# SCH_Beginner_project_2021-06-27.net
KiCad netlist of a schematic drawn in EasyEDA
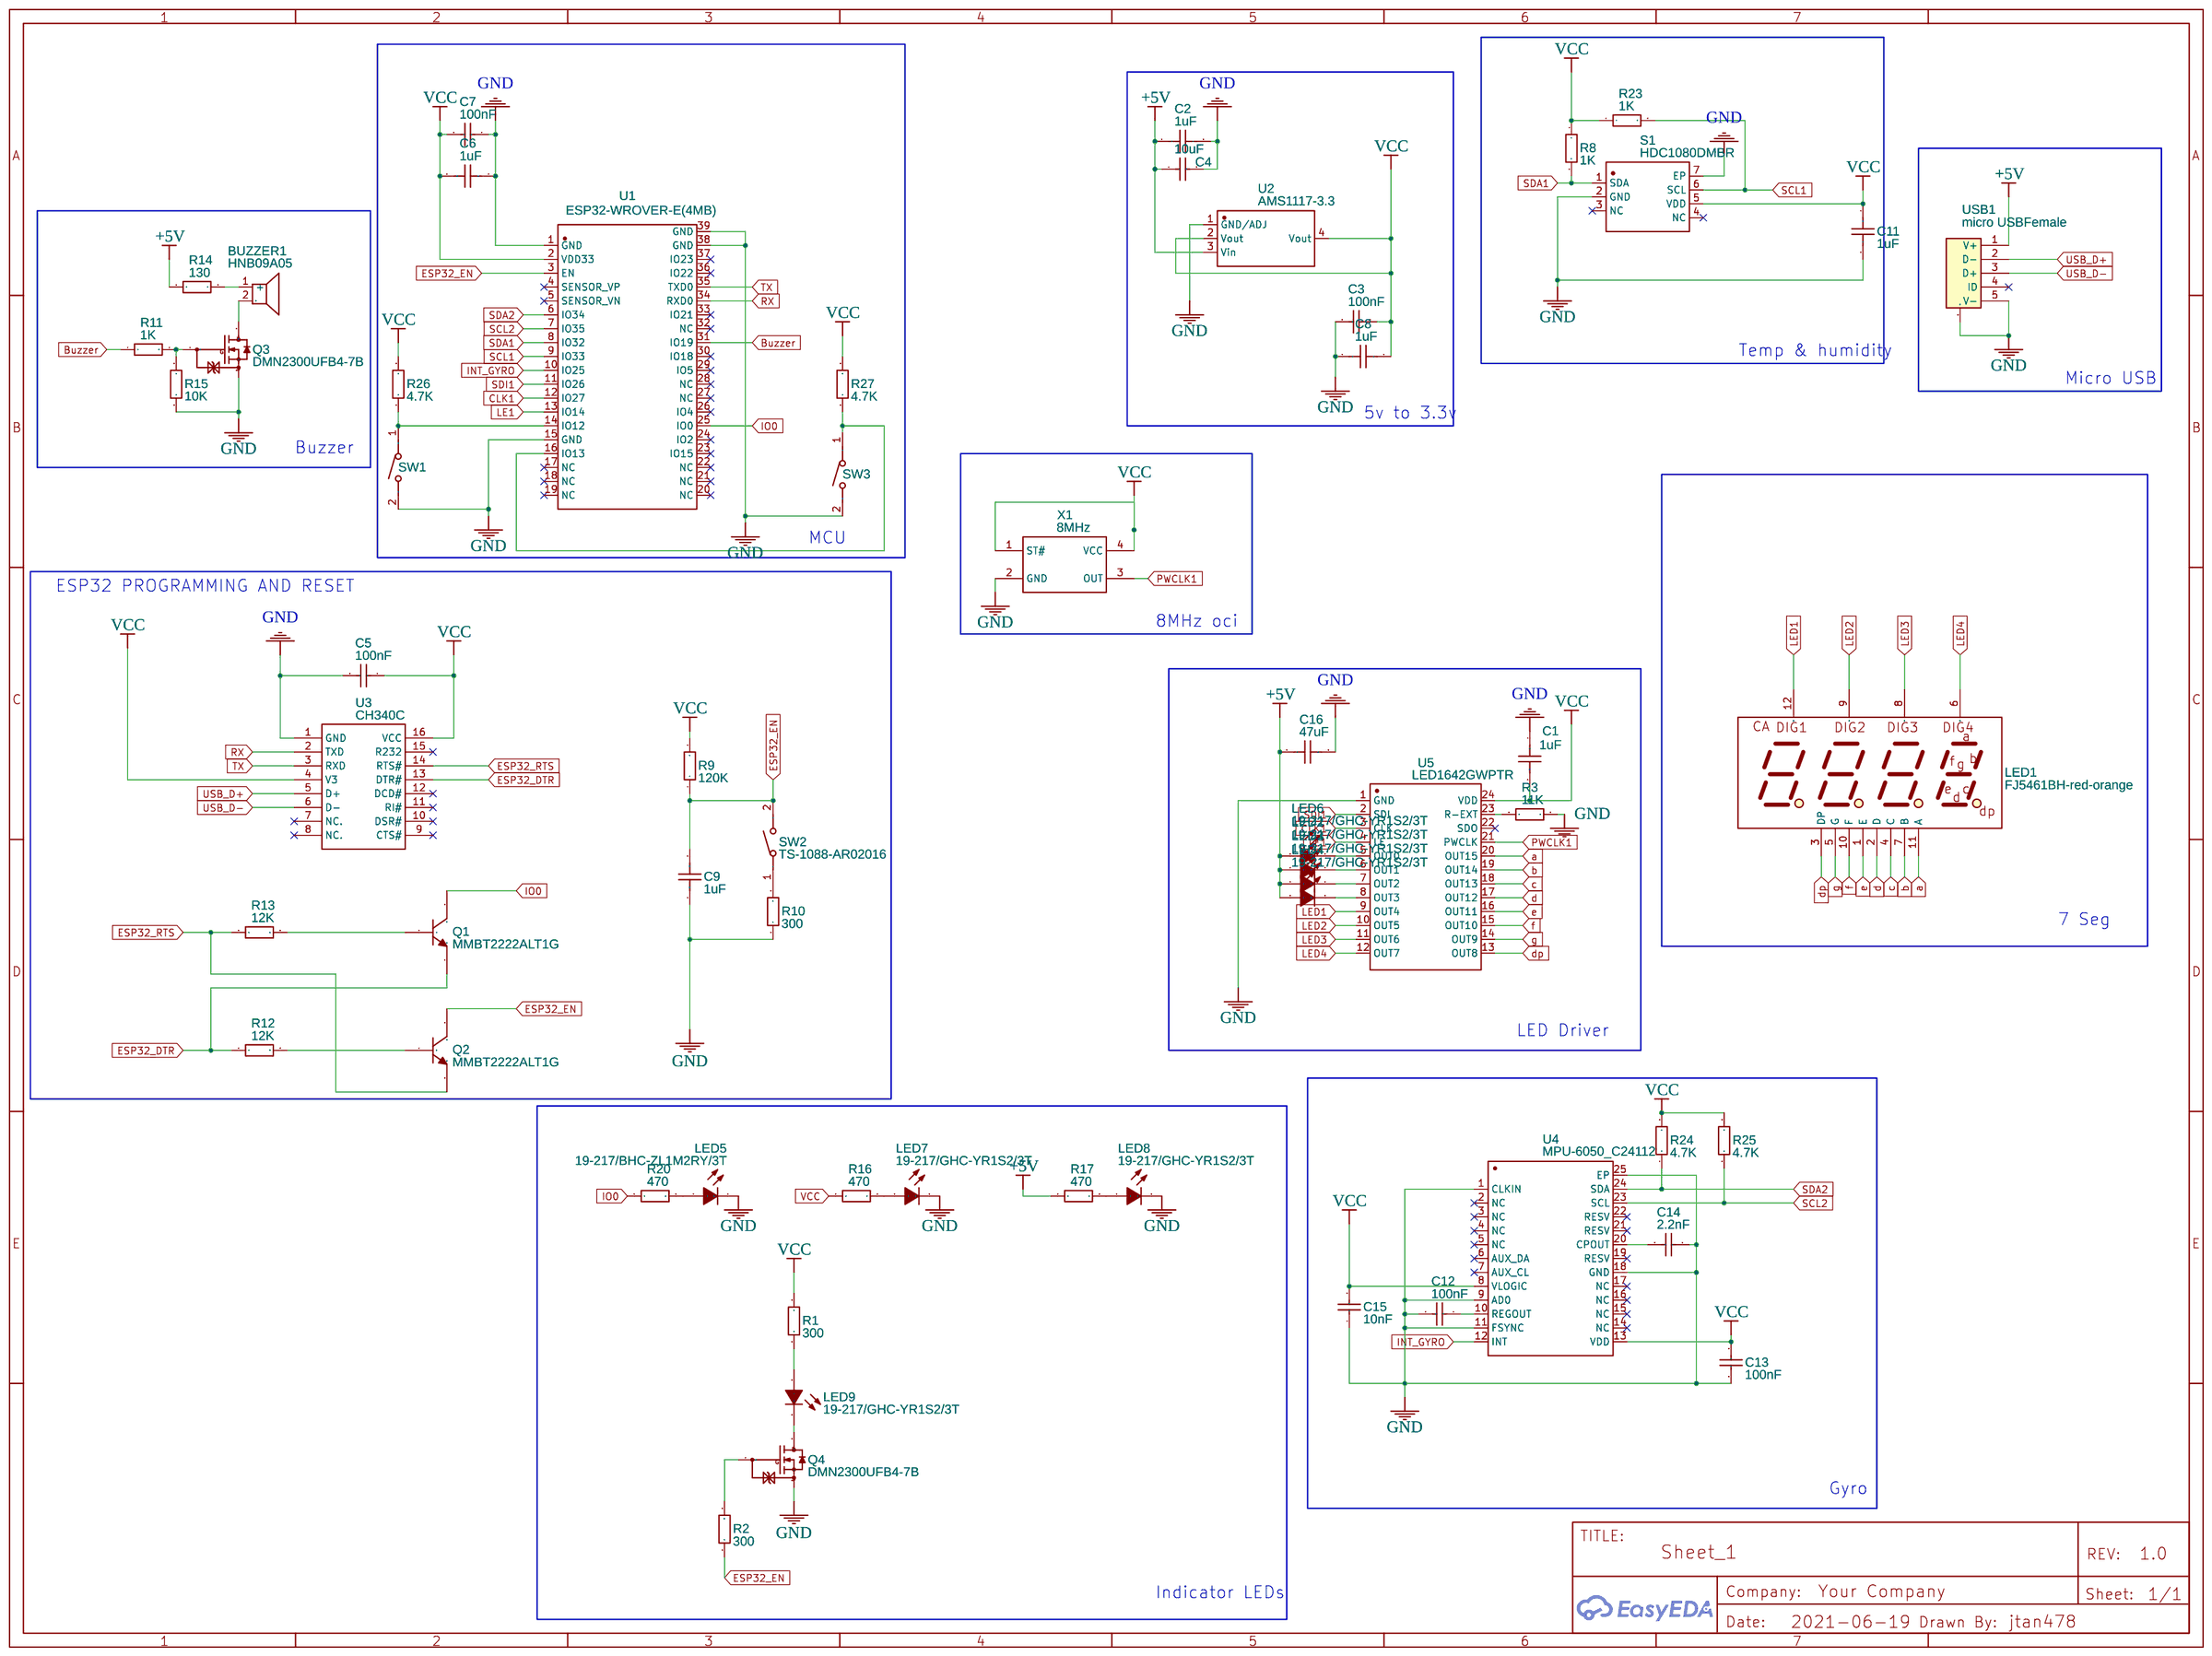
[diagram p0: schematic sheet]

(export (version "E")
  (design (tool "Eeschema 10.0.6"))
  (components
    (comp (ref "BUZZER1")
      (value "HNB09A05")
      (fields (field (name "BOM_Supplier Part") "C96493"))
      (libsource (lib "") (part "HNB09A05"))
    )
    (comp (ref "C1")
      (value "1uF")
      (fields
        (field (name "BOM_Manufacturer Part") "CL05A105KA5NQNC")
        (field (name "BOM_Supplier Part") "C52923")
      )
      (libsource (lib "") (part "CL05A105KA5NQNC"))
    )
    (comp (ref "C2")
      (value "1uF")
      (fields
        (field (name "BOM_Manufacturer Part") "CL05A105KA5NQNC")
        (field (name "BOM_Supplier Part") "C52923")
      )
      (libsource (lib "") (part "CL05A105KA5NQNC_1"))
    )
    (comp (ref "C3")
      (value "100nF")
      (fields
        (field (name "BOM_Manufacturer Part") "CL05B104KO5NNNC")
        (field (name "BOM_Supplier Part") "C1525")
      )
      (libsource (lib "") (part "CL05B104KO5NNNC"))
    )
    (comp (ref "C4")
      (value "10uF")
      (fields
        (field (name "BOM_Manufacturer Part") "CL05A106MQ5NUNC")
        (field (name "BOM_Supplier Part") "C15525")
      )
      (libsource (lib "") (part "CL05A106MQ5NUNC"))
    )
    (comp (ref "C5")
      (value "100nF")
      (fields
        (field (name "BOM_Manufacturer Part") "CL05B104KO5NNNC")
        (field (name "BOM_Supplier Part") "C1525")
      )
      (libsource (lib "") (part "CL05B104KO5NNNC"))
    )
    (comp (ref "C6")
      (value "1uF")
      (fields
        (field (name "BOM_Manufacturer Part") "CL05A105KA5NQNC")
        (field (name "BOM_Supplier Part") "C52923")
      )
      (libsource (lib "") (part "CL05A105KA5NQNC_3"))
    )
    (comp (ref "C7")
      (value "100nF")
      (fields
        (field (name "BOM_Manufacturer Part") "CL05B104KO5NNNC")
        (field (name "BOM_Supplier Part") "C1525")
      )
      (libsource (lib "") (part "CL05B104KO5NNNC"))
    )
    (comp (ref "C8")
      (value "1uF")
      (fields
        (field (name "BOM_Manufacturer Part") "CL05A105KA5NQNC")
        (field (name "BOM_Supplier Part") "C52923")
      )
      (libsource (lib "") (part "CL05A105KA5NQNC_1"))
    )
    (comp (ref "C9")
      (value "1uF")
      (fields
        (field (name "BOM_Manufacturer Part") "CL05A105KA5NQNC")
        (field (name "BOM_Supplier Part") "C52923")
      )
      (libsource (lib "") (part "CL05A105KA5NQNC_2"))
    )
    (comp (ref "C11")
      (value "1uF")
      (fields
        (field (name "BOM_Manufacturer Part") "CL05A105KA5NQNC")
        (field (name "BOM_Supplier Part") "C52923")
      )
      (libsource (lib "") (part "CL05A105KA5NQNC"))
    )
    (comp (ref "C12")
      (value "100nF")
      (fields
        (field (name "BOM_Manufacturer Part") "CL05B104KO5NNNC")
        (field (name "BOM_Supplier Part") "C1525")
      )
      (libsource (lib "") (part "CL05B104KO5NNNC"))
    )
    (comp (ref "C13")
      (value "100nF")
      (fields
        (field (name "BOM_Manufacturer Part") "CL05B104KO5NNNC")
        (field (name "BOM_Supplier Part") "C1525")
      )
      (libsource (lib "") (part "CL05B104KO5NNNC_1"))
    )
    (comp (ref "C14")
      (value "2.2nF")
      (fields
        (field (name "BOM_Manufacturer Part") "0402B222K500NT")
        (field (name "BOM_Supplier Part") "C1531")
      )
      (libsource (lib "") (part "0402B222K500NT"))
    )
    (comp (ref "C15")
      (value "10nF")
      (fields
        (field (name "BOM_Manufacturer Part") "CL05B103KB5NNNC")
        (field (name "BOM_Supplier Part") "C15195")
      )
      (libsource (lib "") (part "CL05B103KB5NNNC"))
    )
    (comp (ref "C16")
      (value "47uF")
      (fields
        (field (name "BOM_Manufacturer Part") "CL31A476MPHNNNE")
        (field (name "BOM_Supplier Part") "C96123")
      )
      (libsource (lib "") (part "CL31A476MPHNNNE"))
    )
    (comp (ref "LED1")
      (value "FJ5461BH-red-orange")
      (fields
        (field (name "BOM_Manufacturer Part") "FJ5461BH 橙红")
        (field (name "BOM_Supplier Part") "C10713")
      )
      (libsource (lib "") (part "FJ5461BH-red-orange"))
    )
    (comp (ref "LED2")
      (value "19-217/GHC-YR1S2/3T")
      (fields (field (name "BOM_Supplier Part") "C72043"))
      (libsource (lib "") (part "19-217/GHC-YR1S2/3T"))
    )
    (comp (ref "LED3")
      (value "19-217/GHC-YR1S2/3T")
      (fields (field (name "BOM_Supplier Part") "C72043"))
      (libsource (lib "") (part "19-217/GHC-YR1S2/3T"))
    )
    (comp (ref "LED4")
      (value "19-217/GHC-YR1S2/3T")
      (fields (field (name "BOM_Supplier Part") "C72043"))
      (libsource (lib "") (part "19-217/GHC-YR1S2/3T"))
    )
    (comp (ref "LED5")
      (value "19-217/BHC-ZL1M2RY/3T")
      (fields (field (name "BOM_Supplier Part") "C72041"))
      (libsource (lib "") (part "19-217/BHC-ZL1M2RY/3T"))
    )
    (comp (ref "LED6")
      (value "19-217/GHC-YR1S2/3T")
      (fields (field (name "BOM_Supplier Part") "C72043"))
      (libsource (lib "") (part "19-217/GHC-YR1S2/3T"))
    )
    (comp (ref "LED7")
      (value "19-217/GHC-YR1S2/3T")
      (fields (field (name "BOM_Supplier Part") "C72043"))
      (libsource (lib "") (part "19-217/GHC-YR1S2/3T"))
    )
    (comp (ref "LED8")
      (value "19-217/GHC-YR1S2/3T")
      (fields (field (name "BOM_Supplier Part") "C72043"))
      (libsource (lib "") (part "19-217/GHC-YR1S2/3T"))
    )
    (comp (ref "LED9")
      (value "19-217/GHC-YR1S2/3T")
      (fields (field (name "BOM_Supplier Part") "C72043"))
      (libsource (lib "") (part "19-217/GHC-YR1S2/3T_1"))
    )
    (comp (ref "Q1")
      (value "MMBT2222ALT1G")
      (fields (field (name "BOM_Supplier Part") "C82460"))
      (libsource (lib "") (part "MMBT2222ALT1G"))
    )
    (comp (ref "Q2")
      (value "MMBT2222ALT1G")
      (fields (field (name "BOM_Supplier Part") "C82460"))
      (libsource (lib "") (part "MMBT2222ALT1G"))
    )
    (comp (ref "Q3")
      (value "DMN2300UFB4-7B")
      (fields (field (name "BOM_Supplier Part") "C154728"))
      (libsource (lib "") (part "DMN2300UFB4-7B"))
    )
    (comp (ref "Q4")
      (value "DMN2300UFB4-7B")
      (fields (field (name "BOM_Supplier Part") "C154728"))
      (libsource (lib "") (part "DMN2300UFB4-7B"))
    )
    (comp (ref "R1")
      (value "300")
      (fields
        (field (name "BOM_Manufacturer Part") "0402WGF3000TCE")
        (field (name "BOM_Supplier Part") "C25102")
      )
      (libsource (lib "") (part "0402WGF3000TCE"))
    )
    (comp (ref "R2")
      (value "300")
      (fields
        (field (name "BOM_Manufacturer Part") "0402WGF3000TCE")
        (field (name "BOM_Supplier Part") "C25102")
      )
      (libsource (lib "") (part "0402WGF3000TCE"))
    )
    (comp (ref "R3")
      (value "11K")
      (fields
        (field (name "BOM_Manufacturer Part") "0603WAF1102T5E")
        (field (name "BOM_Supplier Part") "C25950")
      )
      (libsource (lib "") (part "0603WAF1102T5E"))
    )
    (comp (ref "R8")
      (value "1K")
      (fields
        (field (name "BOM_Manufacturer Part") "0603WAF1001T5E")
        (field (name "BOM_Supplier Part") "C21190")
      )
      (libsource (lib "") (part "0603WAF1001T5E"))
    )
    (comp (ref "R9")
      (value "120K")
      (fields
        (field (name "BOM_Manufacturer Part") "0402WGF1203TCE")
        (field (name "BOM_Supplier Part") "C25750")
      )
      (libsource (lib "") (part "0402WGF1203TCE"))
    )
    (comp (ref "R10")
      (value "300")
      (fields
        (field (name "BOM_Manufacturer Part") "0402WGF3000TCE")
        (field (name "BOM_Supplier Part") "C25102")
      )
      (libsource (lib "") (part "0402WGF3000TCE"))
    )
    (comp (ref "R11")
      (value "1K")
      (fields
        (field (name "BOM_Manufacturer Part") "0603WAF1001T5E")
        (field (name "BOM_Supplier Part") "C21190")
      )
      (libsource (lib "") (part "0603WAF1001T5E_1"))
    )
    (comp (ref "R12")
      (value "12K")
      (fields
        (field (name "BOM_Manufacturer Part") "0402WGF1202TCE")
        (field (name "BOM_Supplier Part") "C25752")
      )
      (libsource (lib "") (part "0402WGF1202TCE"))
    )
    (comp (ref "R13")
      (value "12K")
      (fields
        (field (name "BOM_Manufacturer Part") "0402WGF1202TCE")
        (field (name "BOM_Supplier Part") "C25752")
      )
      (libsource (lib "") (part "0402WGF1202TCE"))
    )
    (comp (ref "R14")
      (value "130")
      (fields
        (field (name "BOM_Manufacturer Part") "0603WAF1300T5E")
        (field (name "BOM_Supplier Part") "C22796")
      )
      (libsource (lib "") (part "0603WAF1300T5E"))
    )
    (comp (ref "R15")
      (value "10K")
      (fields
        (field (name "BOM_Manufacturer Part") "0603WAF1002T5E")
        (field (name "BOM_Supplier Part") "C25804")
      )
      (libsource (lib "") (part "0603WAF1002T5E"))
    )
    (comp (ref "R16")
      (value "470")
      (fields
        (field (name "BOM_Manufacturer Part") "0402WGF4700TCE")
        (field (name "BOM_Supplier Part") "C25117")
      )
      (libsource (lib "") (part "0402WGF4700TCE"))
    )
    (comp (ref "R17")
      (value "470")
      (fields
        (field (name "BOM_Manufacturer Part") "0402WGF4700TCE")
        (field (name "BOM_Supplier Part") "C25117")
      )
      (libsource (lib "") (part "0402WGF4700TCE"))
    )
    (comp (ref "R20")
      (value "470")
      (fields
        (field (name "BOM_Manufacturer Part") "0402WGF4700TCE")
        (field (name "BOM_Supplier Part") "C25117")
      )
      (libsource (lib "") (part "0402WGF4700TCE"))
    )
    (comp (ref "R23")
      (value "1K")
      (fields
        (field (name "BOM_Manufacturer Part") "0603WAF1001T5E")
        (field (name "BOM_Supplier Part") "C21190")
      )
      (libsource (lib "") (part "0603WAF1001T5E_1"))
    )
    (comp (ref "R24")
      (value "4.7K")
      (fields
        (field (name "BOM_Manufacturer Part") "0402WGF4701TCE")
        (field (name "BOM_Supplier Part") "C25900")
      )
      (libsource (lib "") (part "0402WGF4701TCE"))
    )
    (comp (ref "R25")
      (value "4.7K")
      (fields
        (field (name "BOM_Manufacturer Part") "0402WGF4701TCE")
        (field (name "BOM_Supplier Part") "C25900")
      )
      (libsource (lib "") (part "0402WGF4701TCE"))
    )
    (comp (ref "R26")
      (value "4.7K")
      (fields
        (field (name "BOM_Manufacturer Part") "0402WGF4701TCE")
        (field (name "BOM_Supplier Part") "C25900")
      )
      (libsource (lib "") (part "0402WGF4701TCE"))
    )
    (comp (ref "R27")
      (value "4.7K")
      (fields
        (field (name "BOM_Manufacturer Part") "0402WGF4701TCE")
        (field (name "BOM_Supplier Part") "C25900")
      )
      (libsource (lib "") (part "0402WGF4701TCE"))
    )
    (comp (ref "S1")
      (value "HDC1080DMBR")
      (fields (field (name "BOM_Supplier Part") "C82227"))
      (libsource (lib "") (part "HDC1080DMBR"))
    )
    (comp (ref "SW1")
      (value "TS-1088-AR02016")
      (fields (field (name "BOM_Supplier Part") "C720477"))
      (libsource (lib "") (part "TS-1088-AR02016_1"))
    )
    (comp (ref "SW2")
      (value "TS-1088-AR02016")
      (fields (field (name "BOM_Supplier Part") "C720477"))
      (libsource (lib "") (part "TS-1088-AR02016"))
    )
    (comp (ref "SW3")
      (value "TS-1088-AR02016")
      (fields (field (name "BOM_Supplier Part") "C720477"))
      (libsource (lib "") (part "TS-1088-AR02016_1"))
    )
    (comp (ref "U1")
      (value "ESP32-WROVER-E(4MB)")
      (fields (field (name "BOM_Supplier Part") "C529587"))
      (libsource (lib "") (part "ESP32-WROVER-E(4MB)"))
    )
    (comp (ref "U2")
      (value "AMS1117-3.3")
      (fields (field (name "BOM_Supplier Part") "C6186"))
      (libsource (lib "") (part "AMS1117-3.3"))
    )
    (comp (ref "U3")
      (value "CH340C")
      (fields (field (name "BOM_Supplier Part") "C84681"))
      (libsource (lib "") (part "CH340C"))
    )
    (comp (ref "U4")
      (value "MPU-6050_C24112")
      (fields (field (name "BOM_Manufacturer Part") "MPU-6050") (field (name "BOM_Supplier Part") "C24112"))
      (libsource (lib "") (part "MPU-6050_C24112"))
    )
    (comp (ref "U5")
      (value "LED1642GWPTR")
      (fields (field (name "BOM_Supplier Part") "C131193"))
      (libsource (lib "") (part "LED1642GWPTR"))
    )
    (comp (ref "USB1")
      (value "micro USBFemale")
      (fields (field (name "BOM_Supplier Part") "C10418"))
      (libsource (lib "") (part "micro USBFemale"))
    )
    (comp (ref "X1")
      (value "8MHz")
      (fields
        (field (name "BOM_Manufacturer Part") "Q33310F70055100")
        (field (name "BOM_Supplier Part") "C70556")
      )
      (libsource (lib "") (part "Q33310F70055100"))
    )
  )
  (nets
    (net (code "1") (name "+5V") (class "Default")
      (node (ref "C16") (pin "1") (pinfunction "1_1") (pintype "unspecified"))
      (node (ref "C2") (pin "1") (pinfunction "1_1") (pintype "unspecified"))
      (node (ref "C4") (pin "1") (pinfunction "1_1") (pintype "input"))
      (node (ref "LED2") (pin "1") (pinfunction "A_1") (pintype "input"))
      (node (ref "LED3") (pin "1") (pinfunction "A_1") (pintype "input"))
      (node (ref "LED4") (pin "1") (pinfunction "A_1") (pintype "input"))
      (node (ref "LED6") (pin "1") (pinfunction "A_1") (pintype "input"))
      (node (ref "R14") (pin "1") (pinfunction "1_1") (pintype "input"))
      (node (ref "R17") (pin "1") (pinfunction "1_1") (pintype "input"))
      (node (ref "U2") (pin "3") (pinfunction "Vin_3") (pintype "unspecified"))
      (node (ref "USB1") (pin "1") (pinfunction "V+_1") (pintype "unspecified"))
    )
    (net (code "2") (name "Buzzer") (class "Default")
      (node (ref "R11") (pin "1") (pinfunction "1_1") (pintype "input"))
      (node (ref "U1") (pin "31") (pinfunction "IO19_31") (pintype "unspecified"))
    )
    (net (code "3") (name "CLK1") (class "Default")
      (node (ref "U1") (pin "12") (pinfunction "IO27_12") (pintype "unspecified"))
      (node (ref "U5") (pin "3") (pinfunction "CLK_3") (pintype "unspecified"))
    )
    (net (code "4") (name "ESP32_DTR") (class "Default")
      (node (ref "Q1") (pin "2") (pinfunction "E_2") (pintype "unspecified"))
      (node (ref "R12") (pin "1") (pinfunction "1_1") (pintype "input"))
      (node (ref "U3") (pin "13") (pinfunction "DTR#_13") (pintype "unspecified"))
    )
    (net (code "5") (name "ESP32_EN") (class "Default")
      (node (ref "C9") (pin "2") (pinfunction "2_2") (pintype "unspecified"))
      (node (ref "Q2") (pin "3") (pinfunction "C_3") (pintype "unspecified"))
      (node (ref "R2") (pin "1") (pinfunction "1_1") (pintype "input"))
      (node (ref "R9") (pin "1") (pinfunction "1_1") (pintype "input"))
      (node (ref "SW2") (pin "2") (pinfunction "2_2") (pintype "unspecified"))
      (node (ref "U1") (pin "3") (pinfunction "EN_3") (pintype "unspecified"))
    )
    (net (code "6") (name "ESP32_RTS") (class "Default")
      (node (ref "Q2") (pin "2") (pinfunction "E_2") (pintype "unspecified"))
      (node (ref "R13") (pin "1") (pinfunction "1_1") (pintype "input"))
      (node (ref "U3") (pin "14") (pinfunction "RTS#_14") (pintype "unspecified"))
    )
    (net (code "7") (name "GND") (class "Default")
      (node (ref "C1") (pin "1") (pinfunction "1_1") (pintype "unspecified"))
      (node (ref "C11") (pin "2") (pinfunction "2_2") (pintype "unspecified"))
      (node (ref "C12") (pin "2") (pinfunction "2_2") (pintype "input"))
      (node (ref "C13") (pin "2") (pinfunction "2_2") (pintype "input"))
      (node (ref "C14") (pin "1") (pinfunction "1_1") (pintype "input"))
      (node (ref "C15") (pin "1") (pinfunction "1_1") (pintype "input"))
      (node (ref "C16") (pin "2") (pinfunction "2_2") (pintype "unspecified"))
      (node (ref "C2") (pin "2") (pinfunction "2_2") (pintype "unspecified"))
      (node (ref "C3") (pin "2") (pinfunction "2_2") (pintype "input"))
      (node (ref "C4") (pin "2") (pinfunction "2_2") (pintype "input"))
      (node (ref "C5") (pin "2") (pinfunction "2_2") (pintype "input"))
      (node (ref "C6") (pin "1") (pinfunction "1_1") (pintype "unspecified"))
      (node (ref "C7") (pin "1") (pinfunction "1_1") (pintype "input"))
      (node (ref "C8") (pin "1") (pinfunction "1_1") (pintype "unspecified"))
      (node (ref "C9") (pin "1") (pinfunction "1_1") (pintype "unspecified"))
      (node (ref "LED5") (pin "2") (pinfunction "C_2") (pintype "input"))
      (node (ref "LED7") (pin "2") (pinfunction "C_2") (pintype "input"))
      (node (ref "LED8") (pin "2") (pinfunction "C_2") (pintype "input"))
      (node (ref "Q3") (pin "3") (pinfunction "S_3") (pintype "unspecified"))
      (node (ref "Q4") (pin "3") (pinfunction "S_3") (pintype "unspecified"))
      (node (ref "R10") (pin "1") (pinfunction "1_1") (pintype "input"))
      (node (ref "R15") (pin "2") (pinfunction "2_2") (pintype "input"))
      (node (ref "R3") (pin "2") (pinfunction "2_2") (pintype "input"))
      (node (ref "S1") (pin "2") (pinfunction "GND_2") (pintype "unspecified"))
      (node (ref "S1") (pin "7") (pinfunction "EP_7") (pintype "unspecified"))
      (node (ref "SW1") (pin "2") (pinfunction "2_2") (pintype "unspecified"))
      (node (ref "SW3") (pin "2") (pinfunction "2_2") (pintype "unspecified"))
      (node (ref "U1") (pin "1") (pinfunction "GND_1") (pintype "unspecified"))
      (node (ref "U1") (pin "15") (pinfunction "GND_15") (pintype "unspecified"))
      (node (ref "U1") (pin "38") (pinfunction "GND_38") (pintype "unspecified"))
      (node (ref "U1") (pin "39") (pinfunction "GND_39") (pintype "unspecified"))
      (node (ref "U2") (pin "1") (pinfunction "GND/ADJ_1") (pintype "unspecified"))
      (node (ref "U3") (pin "1") (pinfunction "GND_1") (pintype "unspecified"))
      (node (ref "U4") (pin "1") (pinfunction "CLKIN_1") (pintype "unspecified"))
      (node (ref "U4") (pin "11") (pinfunction "FSYNC_11") (pintype "unspecified"))
      (node (ref "U4") (pin "18") (pinfunction "GND_18") (pintype "unspecified"))
      (node (ref "U4") (pin "25") (pinfunction "EP_25") (pintype "unspecified"))
      (node (ref "U4") (pin "9") (pinfunction "AD0_9") (pintype "unspecified"))
      (node (ref "U5") (pin "1") (pinfunction "GND_1") (pintype "unspecified"))
      (node (ref "USB1") (pin "0") (pinfunction "MTN_0") (pintype "input"))
      (node (ref "USB1") (pin "5") (pinfunction "V-_5") (pintype "unspecified"))
      (node (ref "X1") (pin "2") (pinfunction "GND_2") (pintype "unspecified"))
    )
    (net (code "8") (name "INT_GYRO") (class "Default")
      (node (ref "U1") (pin "10") (pinfunction "IO25_10") (pintype "unspecified"))
      (node (ref "U4") (pin "12") (pinfunction "INT_12") (pintype "unspecified"))
    )
    (net (code "9") (name "IO0") (class "Default")
      (node (ref "Q1") (pin "3") (pinfunction "C_3") (pintype "unspecified"))
      (node (ref "R20") (pin "1") (pinfunction "1_1") (pintype "input"))
      (node (ref "U1") (pin "25") (pinfunction "IO0_25") (pintype "unspecified"))
    )
    (net (code "10") (name "LE1") (class "Default")
      (node (ref "U1") (pin "13") (pinfunction "IO14_13") (pintype "unspecified"))
      (node (ref "U5") (pin "4") (pinfunction "LE_4") (pintype "unspecified"))
    )
    (net (code "11") (name "LED1") (class "Default")
      (node (ref "LED1") (pin "12") (pinfunction "DIG1_12") (pintype "input"))
      (node (ref "U5") (pin "9") (pinfunction "OUT4_9") (pintype "unspecified"))
    )
    (net (code "12") (name "LED2") (class "Default")
      (node (ref "LED1") (pin "9") (pinfunction "DIG2_9") (pintype "input"))
      (node (ref "U5") (pin "10") (pinfunction "OUT5_10") (pintype "unspecified"))
    )
    (net (code "13") (name "LED3") (class "Default")
      (node (ref "LED1") (pin "8") (pinfunction "DIG3_8") (pintype "input"))
      (node (ref "U5") (pin "11") (pinfunction "OUT6_11") (pintype "unspecified"))
    )
    (net (code "14") (name "LED4") (class "Default")
      (node (ref "LED1") (pin "6") (pinfunction "DIG4_6") (pintype "input"))
      (node (ref "U5") (pin "12") (pinfunction "OUT7_12") (pintype "unspecified"))
    )
    (net (code "15") (name "Net-(BUZZER1-+)") (class "Default")
      (node (ref "BUZZER1") (pin "1") (pinfunction "+_1") (pintype "unspecified"))
      (node (ref "R14") (pin "2") (pinfunction "2_2") (pintype "input"))
    )
    (net (code "16") (name "Net-(LED2-C)") (class "Default")
      (node (ref "LED2") (pin "2") (pinfunction "C_2") (pintype "input"))
      (node (ref "U5") (pin "6") (pinfunction "OUT1_6") (pintype "unspecified"))
    )
    (net (code "17") (name "Net-(LED3-C)") (class "Default")
      (node (ref "LED3") (pin "2") (pinfunction "C_2") (pintype "input"))
      (node (ref "U5") (pin "7") (pinfunction "OUT2_7") (pintype "unspecified"))
    )
    (net (code "18") (name "Net-(LED4-C)") (class "Default")
      (node (ref "LED4") (pin "2") (pinfunction "C_2") (pintype "input"))
      (node (ref "U5") (pin "8") (pinfunction "OUT3_8") (pintype "unspecified"))
    )
    (net (code "19") (name "Net-(LED5-A)") (class "Default")
      (node (ref "LED5") (pin "1") (pinfunction "A_1") (pintype "input"))
      (node (ref "R20") (pin "2") (pinfunction "2_2") (pintype "input"))
    )
    (net (code "20") (name "Net-(LED6-C)") (class "Default")
      (node (ref "LED6") (pin "2") (pinfunction "C_2") (pintype "input"))
      (node (ref "U5") (pin "5") (pinfunction "OUT0_5") (pintype "unspecified"))
    )
    (net (code "21") (name "Net-(LED7-A)") (class "Default")
      (node (ref "LED7") (pin "1") (pinfunction "A_1") (pintype "input"))
      (node (ref "R16") (pin "2") (pinfunction "2_2") (pintype "input"))
    )
    (net (code "22") (name "Net-(LED8-A)") (class "Default")
      (node (ref "LED8") (pin "1") (pinfunction "A_1") (pintype "input"))
      (node (ref "R17") (pin "2") (pinfunction "2_2") (pintype "input"))
    )
    (net (code "23") (name "Net-(LED9-A)") (class "Default")
      (node (ref "LED9") (pin "1") (pinfunction "A_1") (pintype "input"))
      (node (ref "R1") (pin "1") (pinfunction "1_1") (pintype "input"))
    )
    (net (code "24") (name "Net-(LED9-C)") (class "Default")
      (node (ref "LED9") (pin "2") (pinfunction "C_2") (pintype "input"))
      (node (ref "Q4") (pin "2") (pinfunction "D_2") (pintype "unspecified"))
    )
    (net (code "25") (name "Net-(Q1-B)") (class "Default")
      (node (ref "Q1") (pin "1") (pinfunction "B_1") (pintype "unspecified"))
      (node (ref "R13") (pin "2") (pinfunction "2_2") (pintype "input"))
    )
    (net (code "26") (name "Net-(Q2-B)") (class "Default")
      (node (ref "Q2") (pin "1") (pinfunction "B_1") (pintype "unspecified"))
      (node (ref "R12") (pin "2") (pinfunction "2_2") (pintype "input"))
    )
    (net (code "27") (name "Net-(Q3-D)") (class "Default")
      (node (ref "BUZZER1") (pin "2") (pinfunction "2_2") (pintype "unspecified"))
      (node (ref "Q3") (pin "2") (pinfunction "D_2") (pintype "unspecified"))
    )
    (net (code "28") (name "Net-(Q3-G)") (class "Default")
      (node (ref "Q3") (pin "1") (pinfunction "G_1") (pintype "unspecified"))
      (node (ref "R11") (pin "2") (pinfunction "2_2") (pintype "input"))
      (node (ref "R15") (pin "1") (pinfunction "1_1") (pintype "input"))
    )
    (net (code "29") (name "Net-(Q4-G)") (class "Default")
      (node (ref "Q4") (pin "1") (pinfunction "G_1") (pintype "unspecified"))
      (node (ref "R2") (pin "2") (pinfunction "2_2") (pintype "input"))
    )
    (net (code "30") (name "Net-(R10-Pad2)") (class "Default")
      (node (ref "R10") (pin "2") (pinfunction "2_2") (pintype "input"))
      (node (ref "SW2") (pin "1") (pinfunction "1_1") (pintype "unspecified"))
    )
    (net (code "31") (name "Net-(U1-IO12)") (class "Default")
      (node (ref "R26") (pin "1") (pinfunction "1_1") (pintype "input"))
      (node (ref "SW1") (pin "1") (pinfunction "1_1") (pintype "unspecified"))
      (node (ref "U1") (pin "14") (pinfunction "IO12_14") (pintype "unspecified"))
    )
    (net (code "32") (name "Net-(U1-IO13)") (class "Default")
      (node (ref "R27") (pin "1") (pinfunction "1_1") (pintype "input"))
      (node (ref "SW3") (pin "1") (pinfunction "1_1") (pintype "unspecified"))
      (node (ref "U1") (pin "16") (pinfunction "IO13_16") (pintype "unspecified"))
    )
    (net (code "33") (name "Net-(U4-CPOUT)") (class "Default")
      (node (ref "C14") (pin "2") (pinfunction "2_2") (pintype "input"))
      (node (ref "U4") (pin "20") (pinfunction "CPOUT_20") (pintype "unspecified"))
    )
    (net (code "34") (name "Net-(U4-REGOUT)") (class "Default")
      (node (ref "C12") (pin "1") (pinfunction "1_1") (pintype "input"))
      (node (ref "U4") (pin "10") (pinfunction "REGOUT_10") (pintype "unspecified"))
    )
    (net (code "35") (name "Net-(U5-R-EXT)") (class "Default")
      (node (ref "R3") (pin "1") (pinfunction "1_1") (pintype "input"))
      (node (ref "U5") (pin "23") (pinfunction "R-EXT_23") (pintype "unspecified"))
    )
    (net (code "36") (name "PWCLK1") (class "Default")
      (node (ref "U5") (pin "21") (pinfunction "PWCLK_21") (pintype "unspecified"))
      (node (ref "X1") (pin "3") (pinfunction "OUT_3") (pintype "unspecified"))
    )
    (net (code "37") (name "RX") (class "Default")
      (node (ref "U1") (pin "34") (pinfunction "RXD0_34") (pintype "unspecified"))
      (node (ref "U3") (pin "2") (pinfunction "TXD_2") (pintype "unspecified"))
    )
    (net (code "38") (name "SCL1") (class "Default")
      (node (ref "R23") (pin "2") (pinfunction "2_2") (pintype "input"))
      (node (ref "S1") (pin "6") (pinfunction "SCL_6") (pintype "unspecified"))
      (node (ref "U1") (pin "9") (pinfunction "IO33_9") (pintype "unspecified"))
    )
    (net (code "39") (name "SCL2") (class "Default")
      (node (ref "R25") (pin "1") (pinfunction "1_1") (pintype "input"))
      (node (ref "U1") (pin "7") (pinfunction "IO35_7") (pintype "unspecified"))
      (node (ref "U4") (pin "23") (pinfunction "SCL_23") (pintype "unspecified"))
    )
    (net (code "40") (name "SDA1") (class "Default")
      (node (ref "R8") (pin "2") (pinfunction "2_2") (pintype "input"))
      (node (ref "S1") (pin "1") (pinfunction "SDA_1") (pintype "unspecified"))
      (node (ref "U1") (pin "8") (pinfunction "IO32_8") (pintype "unspecified"))
    )
    (net (code "41") (name "SDA2") (class "Default")
      (node (ref "R24") (pin "1") (pinfunction "1_1") (pintype "input"))
      (node (ref "U1") (pin "6") (pinfunction "IO34_6") (pintype "unspecified"))
      (node (ref "U4") (pin "24") (pinfunction "SDA_24") (pintype "unspecified"))
    )
    (net (code "42") (name "SDI1") (class "Default")
      (node (ref "U1") (pin "11") (pinfunction "IO26_11") (pintype "unspecified"))
      (node (ref "U5") (pin "2") (pinfunction "SDI_2") (pintype "unspecified"))
    )
    (net (code "43") (name "TX") (class "Default")
      (node (ref "U1") (pin "35") (pinfunction "TXD0_35") (pintype "unspecified"))
      (node (ref "U3") (pin "3") (pinfunction "RXD_3") (pintype "unspecified"))
    )
    (net (code "44") (name "USB_D+") (class "Default")
      (node (ref "U3") (pin "5") (pinfunction "D+_5") (pintype "unspecified"))
      (node (ref "USB1") (pin "2") (pinfunction "D-_2") (pintype "unspecified"))
    )
    (net (code "45") (name "USB_D-") (class "Default")
      (node (ref "U3") (pin "6") (pinfunction "D-_6") (pintype "unspecified"))
      (node (ref "USB1") (pin "3") (pinfunction "D+_3") (pintype "unspecified"))
    )
    (net (code "46") (name "VCC") (class "Default")
      (node (ref "C1") (pin "2") (pinfunction "2_2") (pintype "unspecified"))
      (node (ref "C11") (pin "1") (pinfunction "1_1") (pintype "unspecified"))
      (node (ref "C13") (pin "1") (pinfunction "1_1") (pintype "input"))
      (node (ref "C15") (pin "2") (pinfunction "2_2") (pintype "input"))
      (node (ref "C3") (pin "1") (pinfunction "1_1") (pintype "input"))
      (node (ref "C5") (pin "1") (pinfunction "1_1") (pintype "input"))
      (node (ref "C6") (pin "2") (pinfunction "2_2") (pintype "unspecified"))
      (node (ref "C7") (pin "2") (pinfunction "2_2") (pintype "input"))
      (node (ref "C8") (pin "2") (pinfunction "2_2") (pintype "unspecified"))
      (node (ref "R1") (pin "2") (pinfunction "2_2") (pintype "input"))
      (node (ref "R16") (pin "1") (pinfunction "1_1") (pintype "input"))
      (node (ref "R23") (pin "1") (pinfunction "1_1") (pintype "input"))
      (node (ref "R24") (pin "2") (pinfunction "2_2") (pintype "input"))
      (node (ref "R25") (pin "2") (pinfunction "2_2") (pintype "input"))
      (node (ref "R26") (pin "2") (pinfunction "2_2") (pintype "input"))
      (node (ref "R27") (pin "2") (pinfunction "2_2") (pintype "input"))
      (node (ref "R8") (pin "1") (pinfunction "1_1") (pintype "input"))
      (node (ref "R9") (pin "2") (pinfunction "2_2") (pintype "input"))
      (node (ref "S1") (pin "5") (pinfunction "VDD_5") (pintype "unspecified"))
      (node (ref "U1") (pin "2") (pinfunction "VDD33_2") (pintype "unspecified"))
      (node (ref "U2") (pin "2") (pinfunction "Vout_2") (pintype "unspecified"))
      (node (ref "U2") (pin "4") (pinfunction "Vout_4") (pintype "unspecified"))
      (node (ref "U3") (pin "16") (pinfunction "VCC_16") (pintype "unspecified"))
      (node (ref "U3") (pin "4") (pinfunction "V3_4") (pintype "unspecified"))
      (node (ref "U4") (pin "13") (pinfunction "VDD_13") (pintype "unspecified"))
      (node (ref "U4") (pin "8") (pinfunction "VLOGIC_8") (pintype "unspecified"))
      (node (ref "U5") (pin "24") (pinfunction "VDD_24") (pintype "unspecified"))
      (node (ref "X1") (pin "1") (pinfunction "ST#_1") (pintype "unspecified"))
      (node (ref "X1") (pin "4") (pinfunction "VCC_4") (pintype "unspecified"))
    )
    (net (code "47") (name "a") (class "Default")
      (node (ref "LED1") (pin "11") (pinfunction "A_11") (pintype "input"))
      (node (ref "U5") (pin "20") (pinfunction "OUT15_20") (pintype "unspecified"))
    )
    (net (code "48") (name "b") (class "Default")
      (node (ref "LED1") (pin "7") (pinfunction "B_7") (pintype "input"))
      (node (ref "U5") (pin "19") (pinfunction "OUT14_19") (pintype "unspecified"))
    )
    (net (code "49") (name "c") (class "Default")
      (node (ref "LED1") (pin "4") (pinfunction "C_4") (pintype "input"))
      (node (ref "U5") (pin "18") (pinfunction "OUT13_18") (pintype "unspecified"))
    )
    (net (code "50") (name "d") (class "Default")
      (node (ref "LED1") (pin "2") (pinfunction "D_2") (pintype "input"))
      (node (ref "U5") (pin "17") (pinfunction "OUT12_17") (pintype "unspecified"))
    )
    (net (code "51") (name "dp") (class "Default")
      (node (ref "LED1") (pin "3") (pinfunction "DP_3") (pintype "input"))
      (node (ref "U5") (pin "13") (pinfunction "OUT8_13") (pintype "unspecified"))
    )
    (net (code "52") (name "e") (class "Default")
      (node (ref "LED1") (pin "1") (pinfunction "E_1") (pintype "input"))
      (node (ref "U5") (pin "16") (pinfunction "OUT11_16") (pintype "unspecified"))
    )
    (net (code "53") (name "f") (class "Default")
      (node (ref "LED1") (pin "10") (pinfunction "F_10") (pintype "input"))
      (node (ref "U5") (pin "15") (pinfunction "OUT10_15") (pintype "unspecified"))
    )
    (net (code "54") (name "g") (class "Default")
      (node (ref "LED1") (pin "5") (pinfunction "G_5") (pintype "input"))
      (node (ref "U5") (pin "14") (pinfunction "OUT9_14") (pintype "unspecified"))
    )
    (net (code "55") (name "unconnected-(S1-NC-Pad3)") (class "Default")
      (node (ref "S1") (pin "3") (pinfunction "NC_3") (pintype "unspecified+no_connect"))
    )
    (net (code "56") (name "unconnected-(S1-NC-Pad4)") (class "Default")
      (node (ref "S1") (pin "4") (pinfunction "NC_4") (pintype "unspecified+no_connect"))
    )
    (net (code "57") (name "unconnected-(U1-IO2-Pad24)") (class "Default")
      (node (ref "U1") (pin "24") (pinfunction "IO2_24") (pintype "unspecified+no_connect"))
    )
    (net (code "58") (name "unconnected-(U1-IO4-Pad26)") (class "Default")
      (node (ref "U1") (pin "26") (pinfunction "IO4_26") (pintype "unspecified+no_connect"))
    )
    (net (code "59") (name "unconnected-(U1-IO5-Pad29)") (class "Default")
      (node (ref "U1") (pin "29") (pinfunction "IO5_29") (pintype "unspecified+no_connect"))
    )
    (net (code "60") (name "unconnected-(U1-IO15-Pad23)") (class "Default")
      (node (ref "U1") (pin "23") (pinfunction "IO15_23") (pintype "unspecified+no_connect"))
    )
    (net (code "61") (name "unconnected-(U1-IO18-Pad30)") (class "Default")
      (node (ref "U1") (pin "30") (pinfunction "IO18_30") (pintype "unspecified+no_connect"))
    )
    (net (code "62") (name "unconnected-(U1-IO21-Pad33)") (class "Default")
      (node (ref "U1") (pin "33") (pinfunction "IO21_33") (pintype "unspecified+no_connect"))
    )
    (net (code "63") (name "unconnected-(U1-IO22-Pad36)") (class "Default")
      (node (ref "U1") (pin "36") (pinfunction "IO22_36") (pintype "unspecified+no_connect"))
    )
    (net (code "64") (name "unconnected-(U1-IO23-Pad37)") (class "Default")
      (node (ref "U1") (pin "37") (pinfunction "IO23_37") (pintype "unspecified+no_connect"))
    )
    (net (code "65") (name "unconnected-(U1-NC-Pad17)") (class "Default")
      (node (ref "U1") (pin "17") (pinfunction "NC_17") (pintype "unspecified+no_connect"))
    )
    (net (code "66") (name "unconnected-(U1-NC-Pad18)") (class "Default")
      (node (ref "U1") (pin "18") (pinfunction "NC_18") (pintype "unspecified+no_connect"))
    )
    (net (code "67") (name "unconnected-(U1-NC-Pad19)") (class "Default")
      (node (ref "U1") (pin "19") (pinfunction "NC_19") (pintype "unspecified+no_connect"))
    )
    (net (code "68") (name "unconnected-(U1-NC-Pad20)") (class "Default")
      (node (ref "U1") (pin "20") (pinfunction "NC_20") (pintype "unspecified+no_connect"))
    )
    (net (code "69") (name "unconnected-(U1-NC-Pad21)") (class "Default")
      (node (ref "U1") (pin "21") (pinfunction "NC_21") (pintype "unspecified+no_connect"))
    )
    (net (code "70") (name "unconnected-(U1-NC-Pad22)") (class "Default")
      (node (ref "U1") (pin "22") (pinfunction "NC_22") (pintype "unspecified+no_connect"))
    )
    (net (code "71") (name "unconnected-(U1-NC-Pad27)") (class "Default")
      (node (ref "U1") (pin "27") (pinfunction "NC_27") (pintype "unspecified+no_connect"))
    )
    (net (code "72") (name "unconnected-(U1-NC-Pad28)") (class "Default")
      (node (ref "U1") (pin "28") (pinfunction "NC_28") (pintype "unspecified+no_connect"))
    )
    (net (code "73") (name "unconnected-(U1-NC-Pad32)") (class "Default")
      (node (ref "U1") (pin "32") (pinfunction "NC_32") (pintype "unspecified+no_connect"))
    )
    (net (code "74") (name "unconnected-(U1-SENSOR_VN-Pad5)") (class "Default")
      (node (ref "U1") (pin "5") (pinfunction "SENSOR_VN_5") (pintype "unspecified+no_connect"))
    )
    (net (code "75") (name "unconnected-(U1-SENSOR_VP-Pad4)") (class "Default")
      (node (ref "U1") (pin "4") (pinfunction "SENSOR_VP_4") (pintype "unspecified+no_connect"))
    )
    (net (code "76") (name "unconnected-(U3-CTS#-Pad9)") (class "Default")
      (node (ref "U3") (pin "9") (pinfunction "CTS#_9") (pintype "unspecified+no_connect"))
    )
    (net (code "77") (name "unconnected-(U3-DCD#-Pad12)") (class "Default")
      (node (ref "U3") (pin "12") (pinfunction "DCD#_12") (pintype "unspecified+no_connect"))
    )
    (net (code "78") (name "unconnected-(U3-DSR#-Pad10)") (class "Default")
      (node (ref "U3") (pin "10") (pinfunction "DSR#_10") (pintype "unspecified+no_connect"))
    )
    (net (code "79") (name "unconnected-(U3-NC.-Pad7)") (class "Default")
      (node (ref "U3") (pin "7") (pinfunction "NC._7") (pintype "unspecified+no_connect"))
    )
    (net (code "80") (name "unconnected-(U3-NC.-Pad8)") (class "Default")
      (node (ref "U3") (pin "8") (pinfunction "NC._8") (pintype "unspecified+no_connect"))
    )
    (net (code "81") (name "unconnected-(U3-R232-Pad15)") (class "Default")
      (node (ref "U3") (pin "15") (pinfunction "R232_15") (pintype "unspecified+no_connect"))
    )
    (net (code "82") (name "unconnected-(U3-RI#-Pad11)") (class "Default")
      (node (ref "U3") (pin "11") (pinfunction "RI#_11") (pintype "unspecified+no_connect"))
    )
    (net (code "83") (name "unconnected-(U4-AUX_CL-Pad7)") (class "Default")
      (node (ref "U4") (pin "7") (pinfunction "AUX_CL_7") (pintype "unspecified+no_connect"))
    )
    (net (code "84") (name "unconnected-(U4-AUX_DA-Pad6)") (class "Default")
      (node (ref "U4") (pin "6") (pinfunction "AUX_DA_6") (pintype "unspecified+no_connect"))
    )
    (net (code "85") (name "unconnected-(U4-NC-Pad2)") (class "Default")
      (node (ref "U4") (pin "2") (pinfunction "NC_2") (pintype "unspecified+no_connect"))
    )
    (net (code "86") (name "unconnected-(U4-NC-Pad3)") (class "Default")
      (node (ref "U4") (pin "3") (pinfunction "NC_3") (pintype "unspecified+no_connect"))
    )
    (net (code "87") (name "unconnected-(U4-NC-Pad4)") (class "Default")
      (node (ref "U4") (pin "4") (pinfunction "NC_4") (pintype "unspecified+no_connect"))
    )
    (net (code "88") (name "unconnected-(U4-NC-Pad5)") (class "Default")
      (node (ref "U4") (pin "5") (pinfunction "NC_5") (pintype "unspecified+no_connect"))
    )
    (net (code "89") (name "unconnected-(U4-NC-Pad14)") (class "Default")
      (node (ref "U4") (pin "14") (pinfunction "NC_14") (pintype "unspecified+no_connect"))
    )
    (net (code "90") (name "unconnected-(U4-NC-Pad15)") (class "Default")
      (node (ref "U4") (pin "15") (pinfunction "NC_15") (pintype "unspecified+no_connect"))
    )
    (net (code "91") (name "unconnected-(U4-NC-Pad16)") (class "Default")
      (node (ref "U4") (pin "16") (pinfunction "NC_16") (pintype "unspecified+no_connect"))
    )
    (net (code "92") (name "unconnected-(U4-NC-Pad17)") (class "Default")
      (node (ref "U4") (pin "17") (pinfunction "NC_17") (pintype "unspecified+no_connect"))
    )
    (net (code "93") (name "unconnected-(U4-RESV-Pad19)") (class "Default")
      (node (ref "U4") (pin "19") (pinfunction "RESV_19") (pintype "unspecified+no_connect"))
    )
    (net (code "94") (name "unconnected-(U4-RESV-Pad21)") (class "Default")
      (node (ref "U4") (pin "21") (pinfunction "RESV_21") (pintype "unspecified+no_connect"))
    )
    (net (code "95") (name "unconnected-(U4-RESV-Pad22)") (class "Default")
      (node (ref "U4") (pin "22") (pinfunction "RESV_22") (pintype "unspecified+no_connect"))
    )
    (net (code "96") (name "unconnected-(U5-SDO-Pad22)") (class "Default")
      (node (ref "U5") (pin "22") (pinfunction "SDO_22") (pintype "unspecified+no_connect"))
    )
    (net (code "97") (name "unconnected-(USB1-ID-Pad4)") (class "Default")
      (node (ref "USB1") (pin "4") (pinfunction "ID_4") (pintype "unspecified+no_connect"))
    )
  )
)
